# signal_generator_schematic_-_top.net
KiCad netlist of a schematic drawn in EAGLE
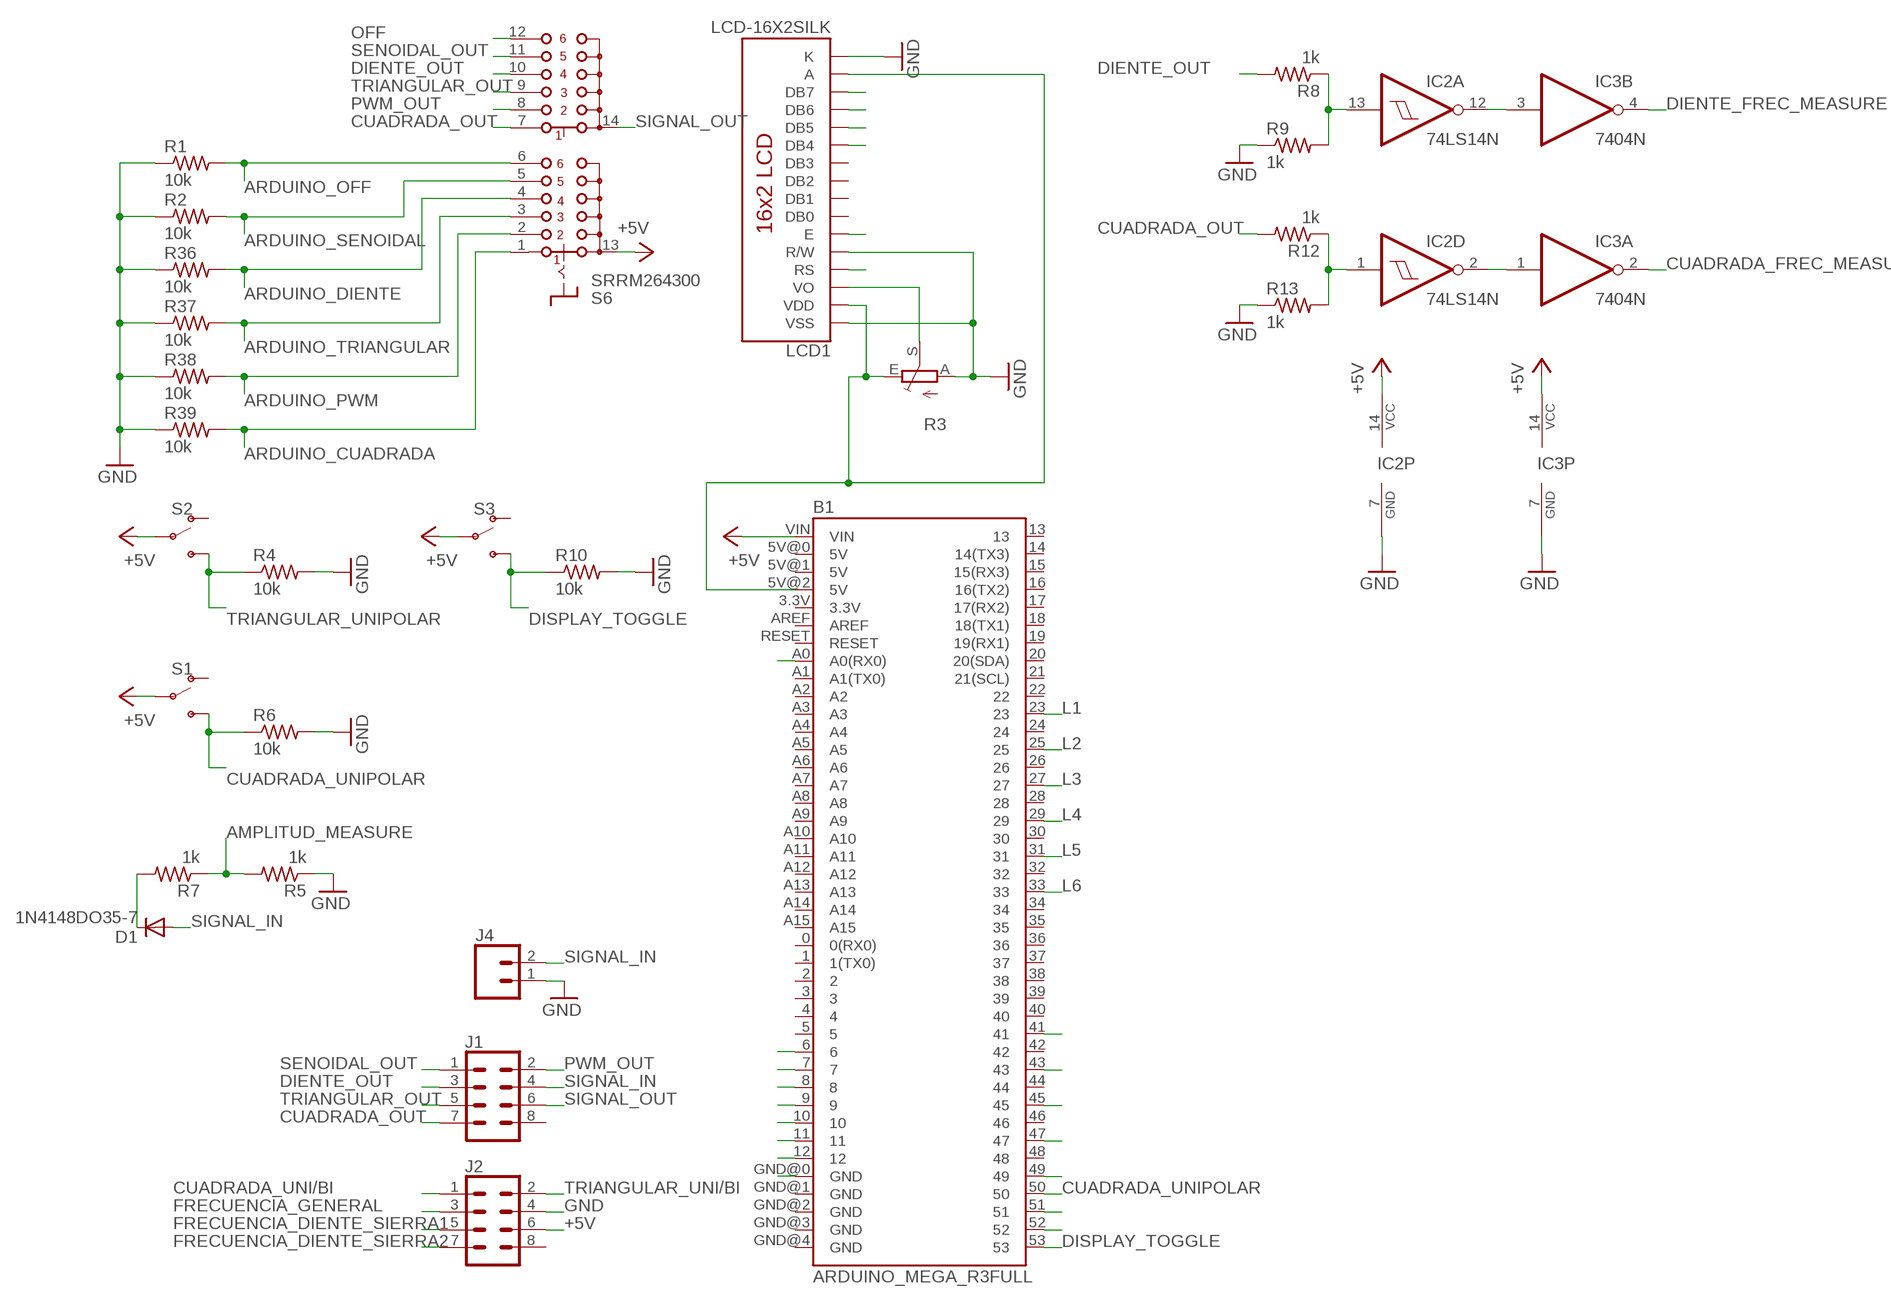
[diagram p0: schematic, sheet 1]

(export (version "E")
  (design (tool "Eeschema 10.0.6"))
  (components
    (comp (ref "B1")
      (value "ARDUINO_MEGA_R3FULL")
      (footprint "eagle-import:ARDUINO_MEGA")
      (libsource (lib "eagle-import") (part "ARDUINO_MEGA_R3FULL"))
    )
    (comp (ref "D1")
      (value "1N4148DO35-7")
      (footprint "eagle-import:DO35-7")
      (libsource (lib "eagle-import") (part "1N4148DO35-7"))
    )
    (comp (ref "IC2")
      (value "74LS14N")
      (footprint "eagle-import:DIL14")
      (libsource (lib "eagle-import") (part "7414NLS"))
    )
    (comp (ref "IC3")
      (value "7404N")
      (footprint "eagle-import:DIL14")
      (libsource (lib "eagle-import") (part "7404N"))
    )
    (comp (ref "J1")
      (value "CONN_04X2")
      (footprint "eagle-import:2X4")
      (libsource (lib "eagle-import") (part "CONN_04X2"))
    )
    (comp (ref "J2")
      (value "CONN_04X2")
      (footprint "eagle-import:2X4")
      (libsource (lib "eagle-import") (part "CONN_04X2"))
    )
    (comp (ref "J4")
      (value "CONN_025MM")
      (footprint "eagle-import:SCREWTERMINAL-5MM-2")
      (libsource (lib "eagle-import") (part "CONN_025MM"))
    )
    (comp (ref "LCD1")
      (value "LCD-16X2SILK")
      (footprint "eagle-import:LCD-16X2")
      (libsource (lib "eagle-import") (part "LCD-16X2SILK"))
    )
    (comp (ref "R1")
      (value "10k")
      (footprint "eagle-import:0207_7")
      (libsource (lib "eagle-import") (part "R-US_0207/7"))
    )
    (comp (ref "R2")
      (value "10k")
      (footprint "eagle-import:0207_7")
      (libsource (lib "eagle-import") (part "R-US_0207/7"))
    )
    (comp (ref "R3")
      (value "TRIM_EU-S63P")
      (footprint "eagle-import:S63P")
      (libsource (lib "eagle-import") (part "TRIM_EU-S63P"))
    )
    (comp (ref "R4")
      (value "10k")
      (footprint "eagle-import:0207_7")
      (libsource (lib "eagle-import") (part "R-US_0207/7"))
    )
    (comp (ref "R5")
      (value "1k")
      (footprint "eagle-import:0207_7")
      (libsource (lib "eagle-import") (part "R-US_0207/7"))
    )
    (comp (ref "R6")
      (value "10k")
      (footprint "eagle-import:0207_7")
      (libsource (lib "eagle-import") (part "R-US_0207/7"))
    )
    (comp (ref "R7")
      (value "1k")
      (footprint "eagle-import:0207_7")
      (libsource (lib "eagle-import") (part "R-US_0207/7"))
    )
    (comp (ref "R8")
      (value "1k")
      (footprint "eagle-import:0207_7")
      (libsource (lib "eagle-import") (part "R-US_0207/7"))
    )
    (comp (ref "R9")
      (value "1k")
      (footprint "eagle-import:0207_7")
      (libsource (lib "eagle-import") (part "R-US_0207/7"))
    )
    (comp (ref "R10")
      (value "10k")
      (footprint "eagle-import:0207_7")
      (libsource (lib "eagle-import") (part "R-US_0207/7"))
    )
    (comp (ref "R12")
      (value "1k")
      (footprint "eagle-import:0207_7")
      (libsource (lib "eagle-import") (part "R-US_0207/7"))
    )
    (comp (ref "R13")
      (value "1k")
      (footprint "eagle-import:0207_7")
      (libsource (lib "eagle-import") (part "R-US_0207/7"))
    )
    (comp (ref "R36")
      (value "10k")
      (footprint "eagle-import:0207_7")
      (libsource (lib "eagle-import") (part "R-US_0207/7"))
    )
    (comp (ref "R37")
      (value "10k")
      (footprint "eagle-import:0207_7")
      (libsource (lib "eagle-import") (part "R-US_0207/7"))
    )
    (comp (ref "R38")
      (value "10k")
      (footprint "eagle-import:0207_7")
      (libsource (lib "eagle-import") (part "R-US_0207/7"))
    )
    (comp (ref "R39")
      (value "10k")
      (footprint "eagle-import:0207_7")
      (libsource (lib "eagle-import") (part "R-US_0207/7"))
    )
    (comp (ref "S1")
      (value "SWITCH-SPDT-PTH-11.6X4.0MM")
      (footprint "eagle-import:SWITCH_SPDT_PTH_11.6X4.0MM")
      (libsource (lib "eagle-import") (part "SWITCH-SPDT-PTH-11.6X4.0MM"))
    )
    (comp (ref "S2")
      (value "SWITCH-SPDT-PTH-11.6X4.0MM")
      (footprint "eagle-import:SWITCH_SPDT_PTH_11.6X4.0MM")
      (libsource (lib "eagle-import") (part "SWITCH-SPDT-PTH-11.6X4.0MM"))
    )
    (comp (ref "S3")
      (value "SWITCH-SPDT-PTH-11.6X4.0MM")
      (footprint "eagle-import:SWITCH_SPDT_PTH_11.6X4.0MM")
      (libsource (lib "eagle-import") (part "SWITCH-SPDT-PTH-11.6X4.0MM"))
    )
    (comp (ref "S6")
      (value "SRRM264300")
      (footprint "eagle-import:SRRM264300")
      (libsource (lib "eagle-import") (part "SRRM264300"))
    )
  )
  (nets
    (net (code "1") (name "+5V") (class "Default")
      (node (ref "B1") (pin "VIN") (pinfunction "VIN_VIN") (pintype "bidirectional"))
      (node (ref "IC2") (pin "14") (pinfunction "VCC_14") (pintype "power_in"))
      (node (ref "IC3") (pin "14") (pinfunction "VCC_14") (pintype "power_in"))
      (node (ref "J2") (pin "6") (pinfunction "6_6") (pintype "passive"))
      (node (ref "S1") (pin "2") (pinfunction "P_2") (pintype "passive"))
      (node (ref "S2") (pin "2") (pinfunction "P_2") (pintype "passive"))
      (node (ref "S3") (pin "2") (pinfunction "P_2") (pintype "passive"))
      (node (ref "S6") (pin "13") (pinfunction "A_13") (pintype "passive"))
    )
    (net (code "2") (name "/AMPLITUD_MEASURE") (class "Default")
      (node (ref "R5") (pin "2") (pinfunction "2_2") (pintype "passive"))
      (node (ref "R7") (pin "1") (pinfunction "1_1") (pintype "passive"))
    )
    (net (code "3") (name "/ARDUINO_CUADRADA") (class "Default")
      (node (ref "B1") (pin "41") (pinfunction "41_41") (pintype "bidirectional"))
      (node (ref "R39") (pin "2") (pinfunction "2_2") (pintype "passive"))
      (node (ref "S6") (pin "1") (pinfunction "A1_1") (pintype "passive"))
    )
    (net (code "4") (name "/ARDUINO_DIENTE") (class "Default")
      (node (ref "B1") (pin "47") (pinfunction "47_47") (pintype "bidirectional"))
      (node (ref "R36") (pin "2") (pinfunction "2_2") (pintype "passive"))
      (node (ref "S6") (pin "4") (pinfunction "A4_4") (pintype "passive"))
    )
    (net (code "5") (name "/ARDUINO_OFF") (class "Default")
      (node (ref "B1") (pin "51") (pinfunction "51_51") (pintype "bidirectional"))
      (node (ref "R1") (pin "2") (pinfunction "2_2") (pintype "passive"))
      (node (ref "S6") (pin "6") (pinfunction "A6_6") (pintype "passive"))
    )
    (net (code "6") (name "/ARDUINO_PWM") (class "Default")
      (node (ref "B1") (pin "43") (pinfunction "43_43") (pintype "bidirectional"))
      (node (ref "R38") (pin "2") (pinfunction "2_2") (pintype "passive"))
      (node (ref "S6") (pin "2") (pinfunction "A2_2") (pintype "passive"))
    )
    (net (code "7") (name "/ARDUINO_SENOIDAL") (class "Default")
      (node (ref "B1") (pin "49") (pinfunction "49_49") (pintype "bidirectional"))
      (node (ref "R2") (pin "2") (pinfunction "2_2") (pintype "passive"))
      (node (ref "S6") (pin "5") (pinfunction "A5_5") (pintype "passive"))
    )
    (net (code "8") (name "/ARDUINO_TRIANGULAR") (class "Default")
      (node (ref "B1") (pin "45") (pinfunction "45_45") (pintype "bidirectional"))
      (node (ref "R37") (pin "2") (pinfunction "2_2") (pintype "passive"))
      (node (ref "S6") (pin "3") (pinfunction "A3_3") (pintype "passive"))
    )
    (net (code "9") (name "/CUADRADA_FREC_MEASURE") (class "Default")
      (node (ref "B1") (pin "6") (pinfunction "6_6") (pintype "bidirectional"))
      (node (ref "IC3") (pin "2") (pinfunction "O_2") (pintype "output"))
    )
    (net (code "10") (name "/CUADRADA_OUT") (class "Default")
      (node (ref "J1") (pin "7") (pinfunction "7_7") (pintype "passive"))
      (node (ref "R12") (pin "2") (pinfunction "2_2") (pintype "passive"))
      (node (ref "S6") (pin "7") (pinfunction "C1_7") (pintype "passive"))
    )
    (net (code "11") (name "/CUADRADA_UNIPOLAR") (class "Default")
      (node (ref "B1") (pin "50") (pinfunction "50_50") (pintype "bidirectional"))
      (node (ref "R6") (pin "1") (pinfunction "1_1") (pintype "passive"))
      (node (ref "S1") (pin "3") (pinfunction "S_3") (pintype "passive"))
    )
    (net (code "12") (name "/CUADRADA_UNI{slash}BI") (class "Default")
      (node (ref "B1") (pin "9") (pinfunction "9_9") (pintype "bidirectional"))
      (node (ref "J2") (pin "1") (pinfunction "1_1") (pintype "passive"))
    )
    (net (code "13") (name "/DIENTE_FREC_MEASURE") (class "Default")
      (node (ref "B1") (pin "7") (pinfunction "7_7") (pintype "bidirectional"))
      (node (ref "IC3") (pin "4") (pinfunction "O_4") (pintype "output"))
    )
    (net (code "14") (name "/DIENTE_OUT") (class "Default")
      (node (ref "J1") (pin "3") (pinfunction "3_3") (pintype "passive"))
      (node (ref "R8") (pin "2") (pinfunction "2_2") (pintype "passive"))
      (node (ref "S6") (pin "10") (pinfunction "C4_10") (pintype "passive"))
    )
    (net (code "15") (name "/DISPLAY_TOGGLE") (class "Default")
      (node (ref "B1") (pin "53") (pinfunction "53_53") (pintype "bidirectional"))
      (node (ref "R10") (pin "1") (pinfunction "1_1") (pintype "passive"))
      (node (ref "S3") (pin "3") (pinfunction "S_3") (pintype "passive"))
    )
    (net (code "16") (name "/FRECUENCIA_DIENTE_SIERRA1") (class "Default")
      (node (ref "B1") (pin "11") (pinfunction "11_11") (pintype "bidirectional"))
      (node (ref "J2") (pin "5") (pinfunction "5_5") (pintype "passive"))
    )
    (net (code "17") (name "/FRECUENCIA_DIENTE_SIERRA2") (class "Default")
      (node (ref "B1") (pin "12") (pinfunction "12_12") (pintype "bidirectional"))
      (node (ref "J2") (pin "7") (pinfunction "7_7") (pintype "passive"))
    )
    (net (code "18") (name "/FRECUENCIA_GENERAL") (class "Default")
      (node (ref "B1") (pin "10") (pinfunction "10_10") (pintype "bidirectional"))
      (node (ref "J2") (pin "3") (pinfunction "3_3") (pintype "passive"))
    )
    (net (code "19") (name "/L1") (class "Default")
      (node (ref "B1") (pin "23") (pinfunction "23_23") (pintype "bidirectional"))
      (node (ref "LCD1") (pin "14") (pinfunction "DB7_14") (pintype "bidirectional"))
    )
    (net (code "20") (name "/L2") (class "Default")
      (node (ref "B1") (pin "25") (pinfunction "25_25") (pintype "bidirectional"))
      (node (ref "LCD1") (pin "13") (pinfunction "DB6_13") (pintype "bidirectional"))
    )
    (net (code "21") (name "/L3") (class "Default")
      (node (ref "B1") (pin "27") (pinfunction "27_27") (pintype "bidirectional"))
      (node (ref "LCD1") (pin "12") (pinfunction "DB5_12") (pintype "bidirectional"))
    )
    (net (code "22") (name "/L4") (class "Default")
      (node (ref "B1") (pin "29") (pinfunction "29_29") (pintype "bidirectional"))
      (node (ref "LCD1") (pin "11") (pinfunction "DB4_11") (pintype "bidirectional"))
    )
    (net (code "23") (name "/L5") (class "Default")
      (node (ref "B1") (pin "31") (pinfunction "31_31") (pintype "bidirectional"))
      (node (ref "LCD1") (pin "6") (pinfunction "E_6") (pintype "input"))
    )
    (net (code "24") (name "/L6") (class "Default")
      (node (ref "B1") (pin "33") (pinfunction "33_33") (pintype "bidirectional"))
      (node (ref "LCD1") (pin "4") (pinfunction "RS_4") (pintype "input"))
    )
    (net (code "25") (name "/OFF") (class "Default")
      (node (ref "S6") (pin "12") (pinfunction "C6_12") (pintype "passive"))
    )
    (net (code "26") (name "/PWM_OUT") (class "Default")
      (node (ref "J1") (pin "2") (pinfunction "2_2") (pintype "passive"))
      (node (ref "S6") (pin "8") (pinfunction "C2_8") (pintype "passive"))
    )
    (net (code "27") (name "/SENOIDAL_OUT") (class "Default")
      (node (ref "J1") (pin "1") (pinfunction "1_1") (pintype "passive"))
      (node (ref "S6") (pin "11") (pinfunction "C5_11") (pintype "passive"))
    )
    (net (code "28") (name "/SIGNAL_IN") (class "Default")
      (node (ref "D1") (pin "A") (pinfunction "A_A") (pintype "passive"))
      (node (ref "J1") (pin "4") (pinfunction "4_4") (pintype "passive"))
      (node (ref "J4") (pin "2") (pinfunction "2_2") (pintype "passive"))
    )
    (net (code "29") (name "/SIGNAL_OUT") (class "Default")
      (node (ref "J1") (pin "6") (pinfunction "6_6") (pintype "passive"))
      (node (ref "S6") (pin "14") (pinfunction "C_14") (pintype "passive"))
    )
    (net (code "30") (name "/TRIANGULAR_OUT") (class "Default")
      (node (ref "J1") (pin "5") (pinfunction "5_5") (pintype "passive"))
      (node (ref "S6") (pin "9") (pinfunction "C3_9") (pintype "passive"))
    )
    (net (code "31") (name "/TRIANGULAR_UNIPOLAR") (class "Default")
      (node (ref "B1") (pin "52") (pinfunction "52_52") (pintype "bidirectional"))
      (node (ref "R4") (pin "1") (pinfunction "1_1") (pintype "passive"))
      (node (ref "S2") (pin "3") (pinfunction "S_3") (pintype "passive"))
    )
    (net (code "32") (name "/TRIANGULAR_UNI{slash}BI") (class "Default")
      (node (ref "B1") (pin "8") (pinfunction "8_8") (pintype "bidirectional"))
      (node (ref "J2") (pin "2") (pinfunction "2_2") (pintype "passive"))
    )
    (net (code "33") (name "GND") (class "Default")
      (node (ref "B1") (pin "GND@0") (pinfunction "GND_GND@0") (pintype "bidirectional"))
      (node (ref "IC2") (pin "7") (pinfunction "GND_7") (pintype "power_in"))
      (node (ref "IC3") (pin "7") (pinfunction "GND_7") (pintype "power_in"))
      (node (ref "J2") (pin "4") (pinfunction "4_4") (pintype "passive"))
      (node (ref "J4") (pin "1") (pinfunction "1_1") (pintype "passive"))
      (node (ref "LCD1") (pin "1") (pinfunction "VSS_1") (pintype "power_in"))
      (node (ref "LCD1") (pin "16") (pinfunction "K_16") (pintype "power_in"))
      (node (ref "LCD1") (pin "5") (pinfunction "R/W_5") (pintype "input"))
      (node (ref "R1") (pin "1") (pinfunction "1_1") (pintype "passive"))
      (node (ref "R10") (pin "2") (pinfunction "2_2") (pintype "passive"))
      (node (ref "R13") (pin "1") (pinfunction "1_1") (pintype "passive"))
      (node (ref "R2") (pin "1") (pinfunction "1_1") (pintype "passive"))
      (node (ref "R3") (pin "A") (pinfunction "A_A") (pintype "passive"))
      (node (ref "R36") (pin "1") (pinfunction "1_1") (pintype "passive"))
      (node (ref "R37") (pin "1") (pinfunction "1_1") (pintype "passive"))
      (node (ref "R38") (pin "1") (pinfunction "1_1") (pintype "passive"))
      (node (ref "R39") (pin "1") (pinfunction "1_1") (pintype "passive"))
      (node (ref "R4") (pin "2") (pinfunction "2_2") (pintype "passive"))
      (node (ref "R5") (pin "1") (pinfunction "1_1") (pintype "passive"))
      (node (ref "R6") (pin "2") (pinfunction "2_2") (pintype "passive"))
      (node (ref "R9") (pin "1") (pinfunction "1_1") (pintype "passive"))
    )
    (net (code "34") (name "Net-(D1-PadC)") (class "Default")
      (node (ref "D1") (pin "C") (pinfunction "C_C") (pintype "passive"))
      (node (ref "R7") (pin "2") (pinfunction "2_2") (pintype "passive"))
    )
    (net (code "35") (name "Net-(IC2A-I)") (class "Default")
      (node (ref "IC2") (pin "13") (pinfunction "I_13") (pintype "input"))
      (node (ref "R8") (pin "1") (pinfunction "1_1") (pintype "passive"))
      (node (ref "R9") (pin "2") (pinfunction "2_2") (pintype "passive"))
    )
    (net (code "36") (name "Net-(IC2A-O)") (class "Default")
      (node (ref "IC2") (pin "12") (pinfunction "O_12") (pintype "output"))
      (node (ref "IC3") (pin "3") (pinfunction "I_3") (pintype "input"))
    )
    (net (code "37") (name "Net-(IC2D-I)") (class "Default")
      (node (ref "IC2") (pin "1") (pinfunction "I_1") (pintype "input"))
      (node (ref "R12") (pin "1") (pinfunction "1_1") (pintype "passive"))
      (node (ref "R13") (pin "2") (pinfunction "2_2") (pintype "passive"))
    )
    (net (code "38") (name "Net-(IC2D-O)") (class "Default")
      (node (ref "IC2") (pin "2") (pinfunction "O_2") (pintype "output"))
      (node (ref "IC3") (pin "1") (pinfunction "I_1") (pintype "input"))
    )
    (net (code "39") (name "Net-(LCD1-A)") (class "Default")
      (node (ref "B1") (pin "5V@2") (pinfunction "5V_5V@2") (pintype "bidirectional"))
      (node (ref "LCD1") (pin "15") (pinfunction "A_15") (pintype "power_in"))
      (node (ref "LCD1") (pin "2") (pinfunction "VDD_2") (pintype "power_in"))
      (node (ref "R3") (pin "E") (pinfunction "E_E") (pintype "passive"))
    )
    (net (code "40") (name "Net-(LCD1-VO)") (class "Default")
      (node (ref "LCD1") (pin "3") (pinfunction "VO_3") (pintype "bidirectional"))
      (node (ref "R3") (pin "S") (pinfunction "S_S") (pintype "passive"))
    )
    (net (code "41") (name "unconnected-(B1-0(RX0)-Pad0)") (class "Default")
      (node (ref "B1") (pin "0") (pinfunction "0(RX0)_0") (pintype "bidirectional"))
    )
    (net (code "42") (name "unconnected-(B1-1(TX0)-Pad1)") (class "Default")
      (node (ref "B1") (pin "1") (pinfunction "1(TX0)_1") (pintype "bidirectional"))
    )
    (net (code "43") (name "unconnected-(B1-5V-Pad5V@0)") (class "Default")
      (node (ref "B1") (pin "5V@0") (pinfunction "5V_5V@0") (pintype "bidirectional"))
    )
    (net (code "44") (name "unconnected-(B1-5V-Pad5V@1)") (class "Default")
      (node (ref "B1") (pin "5V@1") (pinfunction "5V_5V@1") (pintype "bidirectional"))
    )
    (net (code "45") (name "unconnected-(B1-14(TX3)-Pad14)") (class "Default")
      (node (ref "B1") (pin "14") (pinfunction "14(TX3)_14") (pintype "bidirectional"))
    )
    (net (code "46") (name "unconnected-(B1-15(RX3)-Pad15)") (class "Default")
      (node (ref "B1") (pin "15") (pinfunction "15(RX3)_15") (pintype "bidirectional"))
    )
    (net (code "47") (name "unconnected-(B1-16(TX2)-Pad16)") (class "Default")
      (node (ref "B1") (pin "16") (pinfunction "16(TX2)_16") (pintype "bidirectional"))
    )
    (net (code "48") (name "unconnected-(B1-17(RX2)-Pad17)") (class "Default")
      (node (ref "B1") (pin "17") (pinfunction "17(RX2)_17") (pintype "bidirectional"))
    )
    (net (code "49") (name "unconnected-(B1-18(TX1)-Pad18)") (class "Default")
      (node (ref "B1") (pin "18") (pinfunction "18(TX1)_18") (pintype "bidirectional"))
    )
    (net (code "50") (name "unconnected-(B1-19(RX1)-Pad19)") (class "Default")
      (node (ref "B1") (pin "19") (pinfunction "19(RX1)_19") (pintype "bidirectional"))
    )
    (net (code "51") (name "unconnected-(B1-20(SDA)-Pad20)") (class "Default")
      (node (ref "B1") (pin "20") (pinfunction "20(SDA)_20") (pintype "bidirectional"))
    )
    (net (code "52") (name "unconnected-(B1-21(SCL)-Pad21)") (class "Default")
      (node (ref "B1") (pin "21") (pinfunction "21(SCL)_21") (pintype "bidirectional"))
    )
    (net (code "53") (name "unconnected-(B1-A0(RX0)-PadA0)") (class "Default")
      (node (ref "B1") (pin "A0") (pinfunction "A0(RX0)_A0") (pintype "bidirectional"))
    )
    (net (code "54") (name "unconnected-(B1-A1(TX0)-PadA1)") (class "Default")
      (node (ref "B1") (pin "A1") (pinfunction "A1(TX0)_A1") (pintype "bidirectional"))
    )
    (net (code "55") (name "unconnected-(B1-GND-PadGND@1)") (class "Default")
      (node (ref "B1") (pin "GND@1") (pinfunction "GND_GND@1") (pintype "bidirectional"))
    )
    (net (code "56") (name "unconnected-(B1-GND-PadGND@2)") (class "Default")
      (node (ref "B1") (pin "GND@2") (pinfunction "GND_GND@2") (pintype "bidirectional"))
    )
    (net (code "57") (name "unconnected-(B1-GND-PadGND@3)") (class "Default")
      (node (ref "B1") (pin "GND@3") (pinfunction "GND_GND@3") (pintype "bidirectional"))
    )
    (net (code "58") (name "unconnected-(B1-GND-PadGND@4)") (class "Default")
      (node (ref "B1") (pin "GND@4") (pinfunction "GND_GND@4") (pintype "bidirectional"))
    )
    (net (code "59") (name "unconnected-(B1-Pad2)") (class "Default")
      (node (ref "B1") (pin "2") (pinfunction "2_2") (pintype "bidirectional"))
    )
    (net (code "60") (name "unconnected-(B1-Pad3)") (class "Default")
      (node (ref "B1") (pin "3") (pinfunction "3_3") (pintype "bidirectional"))
    )
    (net (code "61") (name "unconnected-(B1-Pad3.3V)") (class "Default")
      (node (ref "B1") (pin "3.3V") (pinfunction "3.3V_3.3V") (pintype "bidirectional"))
    )
    (net (code "62") (name "unconnected-(B1-Pad4)") (class "Default")
      (node (ref "B1") (pin "4") (pinfunction "4_4") (pintype "bidirectional"))
    )
    (net (code "63") (name "unconnected-(B1-Pad5)") (class "Default")
      (node (ref "B1") (pin "5") (pinfunction "5_5") (pintype "bidirectional"))
    )
    (net (code "64") (name "unconnected-(B1-Pad13)") (class "Default")
      (node (ref "B1") (pin "13") (pinfunction "13_13") (pintype "bidirectional"))
    )
    (net (code "65") (name "unconnected-(B1-Pad22)") (class "Default")
      (node (ref "B1") (pin "22") (pinfunction "22_22") (pintype "bidirectional"))
    )
    (net (code "66") (name "unconnected-(B1-Pad24)") (class "Default")
      (node (ref "B1") (pin "24") (pinfunction "24_24") (pintype "bidirectional"))
    )
    (net (code "67") (name "unconnected-(B1-Pad26)") (class "Default")
      (node (ref "B1") (pin "26") (pinfunction "26_26") (pintype "bidirectional"))
    )
    (net (code "68") (name "unconnected-(B1-Pad28)") (class "Default")
      (node (ref "B1") (pin "28") (pinfunction "28_28") (pintype "bidirectional"))
    )
    (net (code "69") (name "unconnected-(B1-Pad30)") (class "Default")
      (node (ref "B1") (pin "30") (pinfunction "30_30") (pintype "bidirectional"))
    )
    (net (code "70") (name "unconnected-(B1-Pad32)") (class "Default")
      (node (ref "B1") (pin "32") (pinfunction "32_32") (pintype "bidirectional"))
    )
    (net (code "71") (name "unconnected-(B1-Pad34)") (class "Default")
      (node (ref "B1") (pin "34") (pinfunction "34_34") (pintype "bidirectional"))
    )
    (net (code "72") (name "unconnected-(B1-Pad35)") (class "Default")
      (node (ref "B1") (pin "35") (pinfunction "35_35") (pintype "bidirectional"))
    )
    (net (code "73") (name "unconnected-(B1-Pad36)") (class "Default")
      (node (ref "B1") (pin "36") (pinfunction "36_36") (pintype "bidirectional"))
    )
    (net (code "74") (name "unconnected-(B1-Pad37)") (class "Default")
      (node (ref "B1") (pin "37") (pinfunction "37_37") (pintype "bidirectional"))
    )
    (net (code "75") (name "unconnected-(B1-Pad38)") (class "Default")
      (node (ref "B1") (pin "38") (pinfunction "38_38") (pintype "bidirectional"))
    )
    (net (code "76") (name "unconnected-(B1-Pad39)") (class "Default")
      (node (ref "B1") (pin "39") (pinfunction "39_39") (pintype "bidirectional"))
    )
    (net (code "77") (name "unconnected-(B1-Pad40)") (class "Default")
      (node (ref "B1") (pin "40") (pinfunction "40_40") (pintype "bidirectional"))
    )
    (net (code "78") (name "unconnected-(B1-Pad42)") (class "Default")
      (node (ref "B1") (pin "42") (pinfunction "42_42") (pintype "bidirectional"))
    )
    (net (code "79") (name "unconnected-(B1-Pad44)") (class "Default")
      (node (ref "B1") (pin "44") (pinfunction "44_44") (pintype "bidirectional"))
    )
    (net (code "80") (name "unconnected-(B1-Pad46)") (class "Default")
      (node (ref "B1") (pin "46") (pinfunction "46_46") (pintype "bidirectional"))
    )
    (net (code "81") (name "unconnected-(B1-Pad48)") (class "Default")
      (node (ref "B1") (pin "48") (pinfunction "48_48") (pintype "bidirectional"))
    )
    (net (code "82") (name "unconnected-(B1-PadA2)") (class "Default")
      (node (ref "B1") (pin "A2") (pinfunction "A2_A2") (pintype "bidirectional"))
    )
    (net (code "83") (name "unconnected-(B1-PadA3)") (class "Default")
      (node (ref "B1") (pin "A3") (pinfunction "A3_A3") (pintype "bidirectional"))
    )
    (net (code "84") (name "unconnected-(B1-PadA4)") (class "Default")
      (node (ref "B1") (pin "A4") (pinfunction "A4_A4") (pintype "bidirectional"))
    )
    (net (code "85") (name "unconnected-(B1-PadA5)") (class "Default")
      (node (ref "B1") (pin "A5") (pinfunction "A5_A5") (pintype "bidirectional"))
    )
    (net (code "86") (name "unconnected-(B1-PadA6)") (class "Default")
      (node (ref "B1") (pin "A6") (pinfunction "A6_A6") (pintype "bidirectional"))
    )
    (net (code "87") (name "unconnected-(B1-PadA7)") (class "Default")
      (node (ref "B1") (pin "A7") (pinfunction "A7_A7") (pintype "bidirectional"))
    )
    (net (code "88") (name "unconnected-(B1-PadA8)") (class "Default")
      (node (ref "B1") (pin "A8") (pinfunction "A8_A8") (pintype "bidirectional"))
    )
    (net (code "89") (name "unconnected-(B1-PadA9)") (class "Default")
      (node (ref "B1") (pin "A9") (pinfunction "A9_A9") (pintype "bidirectional"))
    )
    (net (code "90") (name "unconnected-(B1-PadA10)") (class "Default")
      (node (ref "B1") (pin "A10") (pinfunction "A10_A10") (pintype "bidirectional"))
    )
    (net (code "91") (name "unconnected-(B1-PadA11)") (class "Default")
      (node (ref "B1") (pin "A11") (pinfunction "A11_A11") (pintype "bidirectional"))
    )
    (net (code "92") (name "unconnected-(B1-PadA12)") (class "Default")
      (node (ref "B1") (pin "A12") (pinfunction "A12_A12") (pintype "bidirectional"))
    )
    (net (code "93") (name "unconnected-(B1-PadA13)") (class "Default")
      (node (ref "B1") (pin "A13") (pinfunction "A13_A13") (pintype "bidirectional"))
    )
    (net (code "94") (name "unconnected-(B1-PadA14)") (class "Default")
      (node (ref "B1") (pin "A14") (pinfunction "A14_A14") (pintype "bidirectional"))
    )
    (net (code "95") (name "unconnected-(B1-PadA15)") (class "Default")
      (node (ref "B1") (pin "A15") (pinfunction "A15_A15") (pintype "bidirectional"))
    )
    (net (code "96") (name "unconnected-(B1-PadAREF)") (class "Default")
      (node (ref "B1") (pin "AREF") (pinfunction "AREF_AREF") (pintype "bidirectional"))
    )
    (net (code "97") (name "unconnected-(B1-PadRESET)") (class "Default")
      (node (ref "B1") (pin "RESET") (pinfunction "RESET_RESET") (pintype "bidirectional"))
    )
    (net (code "98") (name "unconnected-(J1-Pad8)") (class "Default")
      (node (ref "J1") (pin "8") (pinfunction "8_8") (pintype "passive"))
    )
    (net (code "99") (name "unconnected-(J2-Pad8)") (class "Default")
      (node (ref "J2") (pin "8") (pinfunction "8_8") (pintype "passive"))
    )
    (net (code "100") (name "unconnected-(LCD1-DB0-Pad7)") (class "Default")
      (node (ref "LCD1") (pin "7") (pinfunction "DB0_7") (pintype "bidirectional"))
    )
    (net (code "101") (name "unconnected-(LCD1-DB1-Pad8)") (class "Default")
      (node (ref "LCD1") (pin "8") (pinfunction "DB1_8") (pintype "bidirectional"))
    )
    (net (code "102") (name "unconnected-(LCD1-DB2-Pad9)") (class "Default")
      (node (ref "LCD1") (pin "9") (pinfunction "DB2_9") (pintype "bidirectional"))
    )
    (net (code "103") (name "unconnected-(LCD1-DB3-Pad10)") (class "Default")
      (node (ref "LCD1") (pin "10") (pinfunction "DB3_10") (pintype "bidirectional"))
    )
    (net (code "104") (name "unconnected-(S1-O-Pad1)") (class "Default")
      (node (ref "S1") (pin "1") (pinfunction "O_1") (pintype "passive"))
    )
    (net (code "105") (name "unconnected-(S2-O-Pad1)") (class "Default")
      (node (ref "S2") (pin "1") (pinfunction "O_1") (pintype "passive"))
    )
    (net (code "106") (name "unconnected-(S3-O-Pad1)") (class "Default")
      (node (ref "S3") (pin "1") (pinfunction "O_1") (pintype "passive"))
    )
  )
)
